# top.net
KiCad netlist of a schematic drawn in Altium Designer
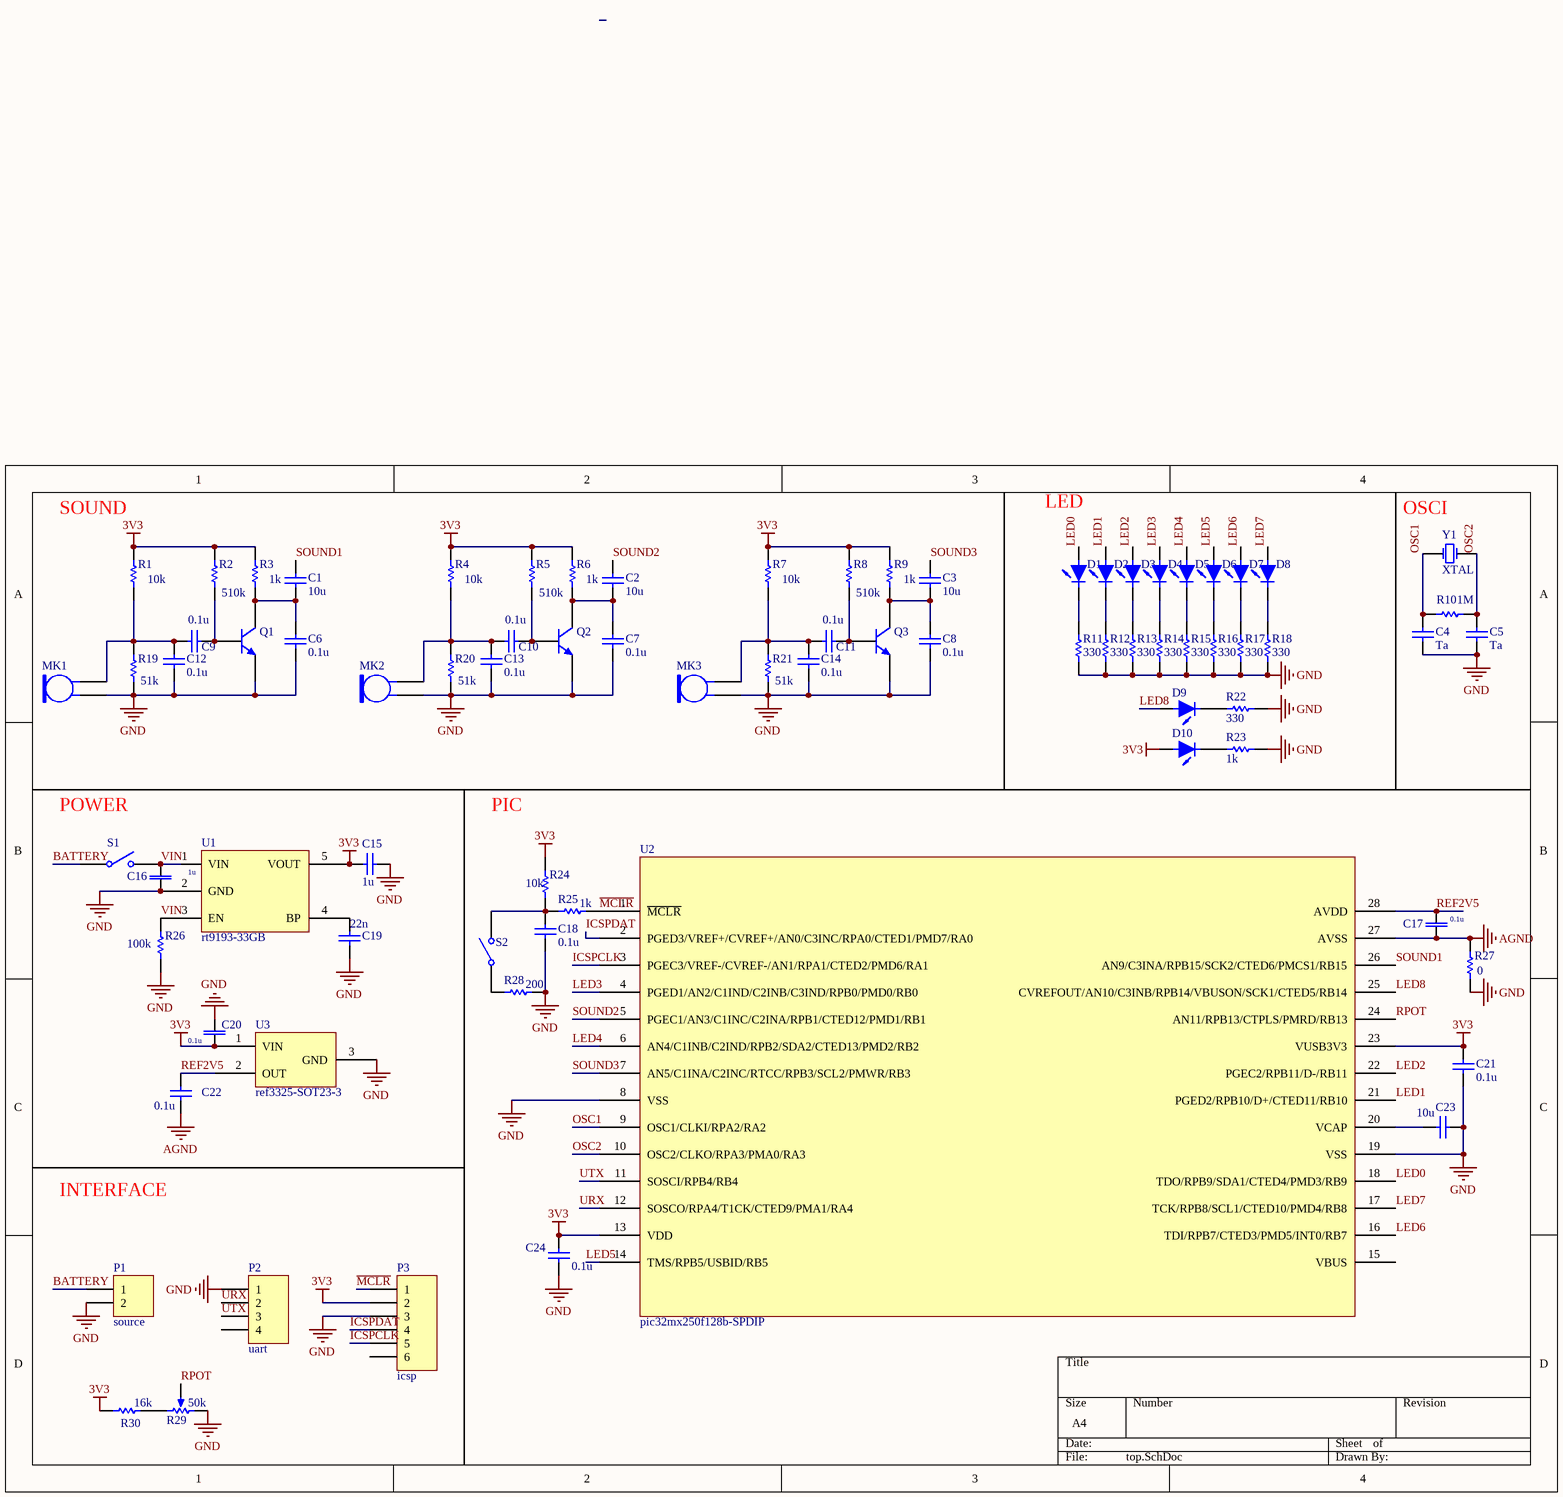
[diagram p0: top.SchDoc]

(export (version "E")
  (design (tool "Eeschema 10.0.6"))
  (components
    (comp (ref "C1")
      (value "10u")
      (footprint "CAPC1608N")
      (description "Capacitor")
      (fields (field (name "Comment") "Cap") (field (name "PUBLISHER") "Altium Limited"))
      (libsource (lib "Miscellaneous Devices") (part "Cap"))
    )
    (comp (ref "C2")
      (value "10u")
      (footprint "CAPC1608N")
      (description "Capacitor")
      (fields (field (name "Comment") "Cap") (field (name "PUBLISHER") "Altium Limited"))
      (libsource (lib "Miscellaneous Devices") (part "Cap"))
    )
    (comp (ref "C3")
      (value "10u")
      (footprint "CAPC1608N")
      (description "Capacitor")
      (fields (field (name "Comment") "Cap") (field (name "PUBLISHER") "Altium Limited"))
      (libsource (lib "Miscellaneous Devices") (part "Cap"))
    )
    (comp (ref "C4")
      (value "Ta")
      (footprint "CAPC1608N")
      (description "Capacitor")
      (fields (field (name "PUBLISHER") "Altium Limited"))
      (libsource (lib "Miscellaneous Devices") (part "Cap"))
    )
    (comp (ref "C5")
      (value "Ta")
      (footprint "CAPC1608N")
      (description "Capacitor")
      (fields (field (name "PUBLISHER") "Altium Limited"))
      (libsource (lib "Miscellaneous Devices") (part "Cap"))
    )
    (comp (ref "C6")
      (value "0.1u")
      (footprint "CAPC1608N")
      (description "Capacitor")
      (fields (field (name "Comment") "Cap") (field (name "PUBLISHER") "Altium Limited"))
      (libsource (lib "Miscellaneous Devices") (part "Cap"))
    )
    (comp (ref "C7")
      (value "0.1u")
      (footprint "CAPC1608N")
      (description "Capacitor")
      (fields (field (name "Comment") "Cap") (field (name "PUBLISHER") "Altium Limited"))
      (libsource (lib "Miscellaneous Devices") (part "Cap"))
    )
    (comp (ref "C8")
      (value "0.1u")
      (footprint "CAPC1608N")
      (description "Capacitor")
      (fields (field (name "Comment") "Cap") (field (name "PUBLISHER") "Altium Limited"))
      (libsource (lib "Miscellaneous Devices") (part "Cap"))
    )
    (comp (ref "C9")
      (value "0.1u")
      (footprint "CAPC1608N")
      (description "Capacitor")
      (fields (field (name "Comment") "Cap") (field (name "PUBLISHER") "Altium Limited"))
      (libsource (lib "Miscellaneous Devices") (part "Cap"))
    )
    (comp (ref "C10")
      (value "0.1u")
      (footprint "CAPC1608N")
      (description "Capacitor")
      (fields (field (name "Comment") "Cap") (field (name "PUBLISHER") "Altium Limited"))
      (libsource (lib "Miscellaneous Devices") (part "Cap"))
    )
    (comp (ref "C11")
      (value "0.1u")
      (footprint "CAPC1608N")
      (description "Capacitor")
      (fields (field (name "Comment") "Cap") (field (name "PUBLISHER") "Altium Limited"))
      (libsource (lib "Miscellaneous Devices") (part "Cap"))
    )
    (comp (ref "C12")
      (value "0.1u")
      (footprint "CAPC1608N")
      (description "Capacitor")
      (fields (field (name "Comment") "Cap") (field (name "PUBLISHER") "Altium Limited"))
      (libsource (lib "Miscellaneous Devices") (part "Cap"))
    )
    (comp (ref "C13")
      (value "0.1u")
      (footprint "CAPC1608N")
      (description "Capacitor")
      (fields (field (name "Comment") "Cap") (field (name "PUBLISHER") "Altium Limited"))
      (libsource (lib "Miscellaneous Devices") (part "Cap"))
    )
    (comp (ref "C14")
      (value "0.1u")
      (footprint "CAPC1608N")
      (description "Capacitor")
      (fields (field (name "Comment") "Cap") (field (name "PUBLISHER") "Altium Limited"))
      (libsource (lib "Miscellaneous Devices") (part "Cap"))
    )
    (comp (ref "C15")
      (value "1u")
      (footprint "CAPC1608N")
      (description "Capacitor")
      (fields (field (name "Comment") "Cap") (field (name "PUBLISHER") "Altium Limited"))
      (libsource (lib "Miscellaneous Devices") (part "Cap"))
    )
    (comp (ref "C16")
      (value "1u")
      (footprint "CAPC1608N")
      (description "Capacitor")
      (fields (field (name "Comment") "Cap") (field (name "PUBLISHER") "Altium Limited"))
      (libsource (lib "") (part "Cap_1"))
    )
    (comp (ref "C17")
      (value "0.1u")
      (footprint "CAPC1608N")
      (description "Capacitor")
      (fields (field (name "Comment") "Cap") (field (name "PUBLISHER") "Altium Limited"))
      (libsource (lib "") (part "Cap_1"))
    )
    (comp (ref "C18")
      (value "0.1u")
      (footprint "CAPC1608N")
      (description "Capacitor")
      (fields (field (name "Comment") "Cap") (field (name "PUBLISHER") "Altium Limited"))
      (libsource (lib "Miscellaneous Devices") (part "Cap"))
    )
    (comp (ref "C19")
      (value "22n")
      (footprint "CAPC1608N")
      (description "Capacitor")
      (fields (field (name "Comment") "Cap") (field (name "PUBLISHER") "Altium Limited"))
      (libsource (lib "Miscellaneous Devices") (part "Cap"))
    )
    (comp (ref "C20")
      (value "0.1u")
      (footprint "CAPC1608N")
      (description "Capacitor")
      (fields (field (name "Comment") "Cap") (field (name "PUBLISHER") "Altium Limited"))
      (libsource (lib "") (part "Cap_1"))
    )
    (comp (ref "C21")
      (value "0.1u")
      (footprint "CAPC1608N")
      (description "Capacitor")
      (fields (field (name "Comment") "Cap") (field (name "PUBLISHER") "Altium Limited"))
      (libsource (lib "Miscellaneous Devices") (part "Cap"))
    )
    (comp (ref "C22")
      (value "0.1u")
      (footprint "CAPC1608N")
      (description "Capacitor")
      (fields (field (name "Comment") "Cap") (field (name "PUBLISHER") "Altium Limited"))
      (libsource (lib "Miscellaneous Devices") (part "Cap"))
    )
    (comp (ref "C23")
      (value "10u")
      (footprint "CAPC1608N")
      (description "Capacitor")
      (fields (field (name "Comment") "Cap") (field (name "PUBLISHER") "Altium Limited"))
      (libsource (lib "Miscellaneous Devices") (part "Cap"))
    )
    (comp (ref "C24")
      (value "0.1u")
      (footprint "CAPC1608N")
      (description "Capacitor")
      (fields (field (name "Comment") "Cap") (field (name "PUBLISHER") "Altium Limited"))
      (libsource (lib "Miscellaneous Devices") (part "Cap"))
    )
    (comp (ref "D1")
      (value "LED2")
      (footprint "CD1608-0603")
      (description "Typical RED, GREEN, YELLOW, AMBER GaAs LED")
      (fields (field (name "PUBLISHER") "Altium Limited"))
      (libsource (lib "Miscellaneous Devices") (part "LED2"))
    )
    (comp (ref "D2")
      (value "LED2")
      (footprint "CD1608-0603")
      (description "Typical RED, GREEN, YELLOW, AMBER GaAs LED")
      (fields (field (name "PUBLISHER") "Altium Limited"))
      (libsource (lib "Miscellaneous Devices") (part "LED2"))
    )
    (comp (ref "D3")
      (value "LED2")
      (footprint "CD1608-0603")
      (description "Typical RED, GREEN, YELLOW, AMBER GaAs LED")
      (fields (field (name "PUBLISHER") "Altium Limited"))
      (libsource (lib "Miscellaneous Devices") (part "LED2"))
    )
    (comp (ref "D4")
      (value "LED2")
      (footprint "CD1608-0603")
      (description "Typical RED, GREEN, YELLOW, AMBER GaAs LED")
      (fields (field (name "PUBLISHER") "Altium Limited"))
      (libsource (lib "Miscellaneous Devices") (part "LED2"))
    )
    (comp (ref "D5")
      (value "LED2")
      (footprint "CD1608-0603")
      (description "Typical RED, GREEN, YELLOW, AMBER GaAs LED")
      (fields (field (name "PUBLISHER") "Altium Limited"))
      (libsource (lib "Miscellaneous Devices") (part "LED2"))
    )
    (comp (ref "D6")
      (value "LED2")
      (footprint "CD1608-0603")
      (description "Typical RED, GREEN, YELLOW, AMBER GaAs LED")
      (fields (field (name "PUBLISHER") "Altium Limited"))
      (libsource (lib "Miscellaneous Devices") (part "LED2"))
    )
    (comp (ref "D7")
      (value "LED2")
      (footprint "CD1608-0603")
      (description "Typical RED, GREEN, YELLOW, AMBER GaAs LED")
      (fields (field (name "PUBLISHER") "Altium Limited"))
      (libsource (lib "Miscellaneous Devices") (part "LED2"))
    )
    (comp (ref "D8")
      (value "LED2")
      (footprint "CD1608-0603")
      (description "Typical RED, GREEN, YELLOW, AMBER GaAs LED")
      (fields (field (name "PUBLISHER") "Altium Limited"))
      (libsource (lib "Miscellaneous Devices") (part "LED2"))
    )
    (comp (ref "D9")
      (value "LED2")
      (footprint "CD1608-0603")
      (description "Typical RED, GREEN, YELLOW, AMBER GaAs LED")
      (fields (field (name "PUBLISHER") "Altium Limited"))
      (libsource (lib "Miscellaneous Devices") (part "LED2"))
    )
    (comp (ref "D10")
      (value "LED2")
      (footprint "CD1608-0603")
      (description "Typical RED, GREEN, YELLOW, AMBER GaAs LED")
      (fields (field (name "PUBLISHER") "Altium Limited"))
      (libsource (lib "Miscellaneous Devices") (part "LED2"))
    )
    (comp (ref "MK1")
      (value "Mic2")
      (footprint "MK")
      (description "Microphone")
      (fields (field (name "PUBLISHER") "Altium Limited"))
      (libsource (lib "Miscellaneous Devices") (part "Mic2"))
    )
    (comp (ref "MK2")
      (value "Mic2")
      (footprint "MK")
      (description "Microphone")
      (fields (field (name "PUBLISHER") "Altium Limited"))
      (libsource (lib "Miscellaneous Devices") (part "Mic2"))
    )
    (comp (ref "MK3")
      (value "Mic2")
      (footprint "MK")
      (description "Microphone")
      (fields (field (name "PUBLISHER") "Altium Limited"))
      (libsource (lib "Miscellaneous Devices") (part "Mic2"))
    )
    (comp (ref "P1")
      (value "source")
      (footprint "HDR1X2")
      (description "Header, 2-Pin")
      (fields (field (name "PUBLISHER") "Altium Limited"))
      (libsource (lib "Miscellaneous Connectors") (part "Header 2"))
    )
    (comp (ref "P2")
      (value "uart")
      (footprint "HDR1X4")
      (description "Header, 4-Pin")
      (fields (field (name "PUBLISHER") "Altium Limited"))
      (libsource (lib "Miscellaneous Connectors") (part "Header 4"))
    )
    (comp (ref "P3")
      (value "icsp")
      (footprint "HDR1X6")
      (description "Header, 6-Pin")
      (fields (field (name "PUBLISHER") "Altium Limited"))
      (libsource (lib "Miscellaneous Connectors") (part "Header 6"))
    )
    (comp (ref "Q1")
      (value "QNPN")
      (footprint "SOT-23B_N")
      (description "NPN Bipolar Transistor")
      (fields (field (name "PUBLISHER") "Altium Limited"))
      (libsource (lib "Miscellaneous Devices") (part "QNPN"))
    )
    (comp (ref "Q2")
      (value "QNPN")
      (footprint "SOT-23B_N")
      (description "NPN Bipolar Transistor")
      (fields (field (name "PUBLISHER") "Altium Limited"))
      (libsource (lib "Miscellaneous Devices") (part "QNPN"))
    )
    (comp (ref "Q3")
      (value "QNPN")
      (footprint "SOT-23B_N")
      (description "NPN Bipolar Transistor")
      (fields (field (name "PUBLISHER") "Altium Limited"))
      (libsource (lib "Miscellaneous Devices") (part "QNPN"))
    )
    (comp (ref "R1")
      (value "10k")
      (footprint "RESC1608N")
      (description "Resistor")
      (fields (field (name "Comment") "Res1") (field (name "PUBLISHER") "Altium Limited"))
      (libsource (lib "Miscellaneous Devices") (part "Res1"))
    )
    (comp (ref "R2")
      (value "510k")
      (footprint "RESC1608N")
      (description "Resistor")
      (fields (field (name "Comment") "Res1") (field (name "PUBLISHER") "Altium Limited"))
      (libsource (lib "Miscellaneous Devices") (part "Res1"))
    )
    (comp (ref "R3")
      (value "1k")
      (footprint "RESC1608N")
      (description "Resistor")
      (fields (field (name "Comment") "Res1") (field (name "PUBLISHER") "Altium Limited"))
      (libsource (lib "Miscellaneous Devices") (part "Res1"))
    )
    (comp (ref "R4")
      (value "10k")
      (footprint "RESC1608N")
      (description "Resistor")
      (fields (field (name "Comment") "Res1") (field (name "PUBLISHER") "Altium Limited"))
      (libsource (lib "Miscellaneous Devices") (part "Res1"))
    )
    (comp (ref "R5")
      (value "510k")
      (footprint "RESC1608N")
      (description "Resistor")
      (fields (field (name "Comment") "Res1") (field (name "PUBLISHER") "Altium Limited"))
      (libsource (lib "Miscellaneous Devices") (part "Res1"))
    )
    (comp (ref "R6")
      (value "1k")
      (footprint "RESC1608N")
      (description "Resistor")
      (fields (field (name "Comment") "Res1") (field (name "PUBLISHER") "Altium Limited"))
      (libsource (lib "Miscellaneous Devices") (part "Res1"))
    )
    (comp (ref "R7")
      (value "10k")
      (footprint "RESC1608N")
      (description "Resistor")
      (fields (field (name "Comment") "Res1") (field (name "PUBLISHER") "Altium Limited"))
      (libsource (lib "Miscellaneous Devices") (part "Res1"))
    )
    (comp (ref "R8")
      (value "510k")
      (footprint "RESC1608N")
      (description "Resistor")
      (fields (field (name "Comment") "Res1") (field (name "PUBLISHER") "Altium Limited"))
      (libsource (lib "Miscellaneous Devices") (part "Res1"))
    )
    (comp (ref "R9")
      (value "1k")
      (footprint "RESC1608N")
      (description "Resistor")
      (fields (field (name "Comment") "Res1") (field (name "PUBLISHER") "Altium Limited"))
      (libsource (lib "Miscellaneous Devices") (part "Res1"))
    )
    (comp (ref "R10")
      (value "1M")
      (footprint "RESC1608N")
      (description "Resistor")
      (fields (field (name "Comment") "Res1") (field (name "PUBLISHER") "Altium Limited"))
      (libsource (lib "Miscellaneous Devices") (part "Res1"))
    )
    (comp (ref "R11")
      (value "330")
      (footprint "RESC1608N")
      (description "Resistor")
      (fields (field (name "Comment") "Res1") (field (name "PUBLISHER") "Altium Limited"))
      (libsource (lib "Miscellaneous Devices") (part "Res1"))
    )
    (comp (ref "R12")
      (value "330")
      (footprint "RESC1608N")
      (description "Resistor")
      (fields (field (name "Comment") "Res1") (field (name "PUBLISHER") "Altium Limited"))
      (libsource (lib "Miscellaneous Devices") (part "Res1"))
    )
    (comp (ref "R13")
      (value "330")
      (footprint "RESC1608N")
      (description "Resistor")
      (fields (field (name "Comment") "Res1") (field (name "PUBLISHER") "Altium Limited"))
      (libsource (lib "Miscellaneous Devices") (part "Res1"))
    )
    (comp (ref "R14")
      (value "330")
      (footprint "RESC1608N")
      (description "Resistor")
      (fields (field (name "Comment") "Res1") (field (name "PUBLISHER") "Altium Limited"))
      (libsource (lib "Miscellaneous Devices") (part "Res1"))
    )
    (comp (ref "R15")
      (value "330")
      (footprint "RESC1608N")
      (description "Resistor")
      (fields (field (name "Comment") "Res1") (field (name "PUBLISHER") "Altium Limited"))
      (libsource (lib "Miscellaneous Devices") (part "Res1"))
    )
    (comp (ref "R16")
      (value "330")
      (footprint "RESC1608N")
      (description "Resistor")
      (fields (field (name "Comment") "Res1") (field (name "PUBLISHER") "Altium Limited"))
      (libsource (lib "Miscellaneous Devices") (part "Res1"))
    )
    (comp (ref "R17")
      (value "330")
      (footprint "RESC1608N")
      (description "Resistor")
      (fields (field (name "Comment") "Res1") (field (name "PUBLISHER") "Altium Limited"))
      (libsource (lib "Miscellaneous Devices") (part "Res1"))
    )
    (comp (ref "R18")
      (value "330")
      (footprint "RESC1608N")
      (description "Resistor")
      (fields (field (name "Comment") "Res1") (field (name "PUBLISHER") "Altium Limited"))
      (libsource (lib "Miscellaneous Devices") (part "Res1"))
    )
    (comp (ref "R19")
      (value "51k")
      (footprint "RESC1608N")
      (description "Resistor")
      (fields (field (name "Comment") "Res1") (field (name "PUBLISHER") "Altium Limited"))
      (libsource (lib "Miscellaneous Devices") (part "Res1"))
    )
    (comp (ref "R20")
      (value "51k")
      (footprint "RESC1608N")
      (description "Resistor")
      (fields (field (name "Comment") "Res1") (field (name "PUBLISHER") "Altium Limited"))
      (libsource (lib "Miscellaneous Devices") (part "Res1"))
    )
    (comp (ref "R21")
      (value "51k")
      (footprint "RESC1608N")
      (description "Resistor")
      (fields (field (name "Comment") "Res1") (field (name "PUBLISHER") "Altium Limited"))
      (libsource (lib "Miscellaneous Devices") (part "Res1"))
    )
    (comp (ref "R22")
      (value "330")
      (footprint "RESC1608N")
      (description "Resistor")
      (fields (field (name "Comment") "Res1") (field (name "PUBLISHER") "Altium Limited"))
      (libsource (lib "Miscellaneous Devices") (part "Res1"))
    )
    (comp (ref "R23")
      (value "1k")
      (footprint "RESC1608N")
      (description "Resistor")
      (fields (field (name "Comment") "Res1") (field (name "PUBLISHER") "Altium Limited"))
      (libsource (lib "Miscellaneous Devices") (part "Res1"))
    )
    (comp (ref "R24")
      (value "10k")
      (footprint "RESC1608N")
      (description "Resistor")
      (fields (field (name "Comment") "Res1") (field (name "PUBLISHER") "Altium Limited"))
      (libsource (lib "Miscellaneous Devices") (part "Res1"))
    )
    (comp (ref "R25")
      (value "1k")
      (footprint "RESC1608N")
      (description "Resistor")
      (fields (field (name "Comment") "Res1") (field (name "PUBLISHER") "Altium Limited"))
      (libsource (lib "Miscellaneous Devices") (part "Res1"))
    )
    (comp (ref "R26")
      (value "100k")
      (footprint "RESC1608N")
      (description "Resistor")
      (fields (field (name "Comment") "Res1") (field (name "PUBLISHER") "Altium Limited"))
      (libsource (lib "Miscellaneous Devices") (part "Res1"))
    )
    (comp (ref "R27")
      (value "0")
      (footprint "RESC1608N")
      (description "Resistor")
      (fields (field (name "Comment") "Res1") (field (name "PUBLISHER") "Altium Limited"))
      (libsource (lib "Miscellaneous Devices") (part "Res1"))
    )
    (comp (ref "R28")
      (value "200")
      (footprint "RESC1608N")
      (description "Resistor")
      (fields (field (name "Comment") "Res1") (field (name "PUBLISHER") "Altium Limited"))
      (libsource (lib "Miscellaneous Devices") (part "Res1"))
    )
    (comp (ref "R29")
      (value "50k")
      (footprint "RPOT")
      (description "Potentiometer")
      (fields (field (name "Comment") "RPot") (field (name "PUBLISHER") "Altium Limited"))
      (libsource (lib "Miscellaneous Devices") (part "RPot"))
    )
    (comp (ref "R30")
      (value "16k")
      (footprint "RESC1608N")
      (description "Resistor")
      (fields (field (name "Comment") "Res1") (field (name "PUBLISHER") "Altium Limited"))
      (libsource (lib "Miscellaneous Devices") (part "Res1"))
    )
    (comp (ref "S1")
      (value "SW-SPST")
      (footprint "PIN3")
      (description "Single-Pole, Single-Throw Switch")
      (fields (field (name "PUBLISHER") "Altium Limited"))
      (libsource (lib "Miscellaneous Devices") (part "SW-SPST"))
    )
    (comp (ref "S2")
      (value "SW-SPST")
      (footprint "sw")
      (description "Single-Pole, Single-Throw Switch")
      (fields (field (name "PUBLISHER") "Altium Limited"))
      (libsource (lib "Miscellaneous Devices") (part "SW-SPST"))
    )
    (comp (ref "U1")
      (value "rt9193-33GB")
      (footprint "SOT23-5_N")
      (description "rt9193")
      (libsource (lib "rt9193") (part "rt9193"))
    )
    (comp (ref "U2")
      (value "pic32mx250f128b-SPDIP")
      (footprint "DIP-28")
      (libsource (lib "Schlib1") (part "pic32mx250f128b"))
    )
    (comp (ref "U3")
      (value "ref3325-SOT23-3")
      (footprint "SOT23-3")
      (description "ref33xx")
      (libsource (lib "ref33xx") (part "ref33xx"))
    )
    (comp (ref "Y1")
      (value "XTAL")
      (footprint "XTAL")
      (description "Crystal Oscillator")
      (fields (field (name "PUBLISHER") "Altium Limited"))
      (libsource (lib "Miscellaneous Devices") (part "XTAL"))
    )
  )
  (nets
    (net (code "1") (name "/BATTERY") (class "Default")
      (node (ref "P1") (pin "1") (pinfunction "1_1") (pintype "passive"))
      (node (ref "S1") (pin "1") (pinfunction "COMMON_1") (pintype "passive"))
    )
    (net (code "2") (name "/ICSPCLK") (class "Default")
      (node (ref "P3") (pin "5") (pinfunction "5_5") (pintype "passive"))
      (node (ref "U2") (pin "3") (pinfunction "PGEC3/VREF-/CVREF-/AN1/RPA1/CTED2/PMD6/RA1_3") (pintype "passive"))
    )
    (net (code "3") (name "/ICSPDAT") (class "Default")
      (node (ref "P3") (pin "4") (pinfunction "4_4") (pintype "passive"))
      (node (ref "U2") (pin "2") (pinfunction "PGED3/VREF+/CVREF+/AN0/C3INC/RPA0/CTED1/PMD7/RA0_2") (pintype "passive"))
    )
    (net (code "4") (name "/LED0") (class "Default")
      (node (ref "D1") (pin "1") (pinfunction "A_1") (pintype "passive"))
      (node (ref "U2") (pin "18") (pinfunction "TDO/RPB9/SDA1/CTED4/PMD3/RB9_18") (pintype "passive"))
    )
    (net (code "5") (name "/LED1") (class "Default")
      (node (ref "D2") (pin "1") (pinfunction "A_1") (pintype "passive"))
      (node (ref "U2") (pin "21") (pinfunction "PGED2/RPB10/D+/CTED11/RB10_21") (pintype "passive"))
    )
    (net (code "6") (name "/LED2") (class "Default")
      (node (ref "D3") (pin "1") (pinfunction "A_1") (pintype "passive"))
      (node (ref "U2") (pin "22") (pinfunction "PGEC2/RPB11/D-/RB11_22") (pintype "passive"))
    )
    (net (code "7") (name "/LED3") (class "Default")
      (node (ref "D4") (pin "1") (pinfunction "A_1") (pintype "passive"))
      (node (ref "U2") (pin "4") (pinfunction "PGED1/AN2/C1IND/C2INB/C3IND/RPB0/PMD0/RB0_4") (pintype "passive"))
    )
    (net (code "8") (name "/LED4") (class "Default")
      (node (ref "D5") (pin "1") (pinfunction "A_1") (pintype "passive"))
      (node (ref "U2") (pin "6") (pinfunction "AN4/C1INB/C2IND/RPB2/SDA2/CTED13/PMD2/RB2_6") (pintype "passive"))
    )
    (net (code "9") (name "/LED5") (class "Default")
      (node (ref "D6") (pin "1") (pinfunction "A_1") (pintype "passive"))
      (node (ref "U2") (pin "14") (pinfunction "TMS/RPB5/USBID/RB5_14") (pintype "passive"))
    )
    (net (code "10") (name "/LED6") (class "Default")
      (node (ref "D7") (pin "1") (pinfunction "A_1") (pintype "passive"))
      (node (ref "U2") (pin "16") (pinfunction "TDI/RPB7/CTED3/PMD5/INT0/RB7_16") (pintype "passive"))
    )
    (net (code "11") (name "/LED7") (class "Default")
      (node (ref "D8") (pin "1") (pinfunction "A_1") (pintype "passive"))
      (node (ref "U2") (pin "17") (pinfunction "TCK/RPB8/SCL1/CTED10/PMD4/RB8_17") (pintype "passive"))
    )
    (net (code "12") (name "/LED8") (class "Default")
      (node (ref "D9") (pin "1") (pinfunction "A_1") (pintype "passive"))
      (node (ref "U2") (pin "25") (pinfunction "CVREFOUT/AN10/C3INB/RPB14/VBUSON/SCK1/CTED5/RB14_25") (pintype "passive"))
    )
    (net (code "13") (name "/OSC1") (class "Default")
      (node (ref "C4") (pin "1") (pinfunction "1_1") (pintype "passive"))
      (node (ref "R10") (pin "1") (pinfunction "1_1") (pintype "passive"))
      (node (ref "U2") (pin "9") (pinfunction "OSC1/CLKI/RPA2/RA2_9") (pintype "passive"))
      (node (ref "Y1") (pin "2") (pinfunction "OSC2_2") (pintype "passive"))
    )
    (net (code "14") (name "/OSC2") (class "Default")
      (node (ref "C5") (pin "1") (pinfunction "1_1") (pintype "passive"))
      (node (ref "R10") (pin "2") (pinfunction "2_2") (pintype "passive"))
      (node (ref "U2") (pin "10") (pinfunction "OSC2/CLKO/RPA3/PMA0/RA3_10") (pintype "passive"))
      (node (ref "Y1") (pin "1") (pinfunction "OSC1_1") (pintype "passive"))
    )
    (net (code "15") (name "/REF2V5") (class "Default")
      (node (ref "C17") (pin "1") (pinfunction "1_1") (pintype "passive"))
      (node (ref "C22") (pin "2") (pinfunction "2_2") (pintype "passive"))
      (node (ref "U2") (pin "28") (pinfunction "AVDD_28") (pintype "passive"))
      (node (ref "U3") (pin "2") (pinfunction "OUT_2") (pintype "passive"))
    )
    (net (code "16") (name "/RPOT") (class "Default")
      (node (ref "R29") (pin "3") (pinfunction "TAP_3") (pintype "passive"))
      (node (ref "U2") (pin "24") (pinfunction "AN11/RPB13/CTPLS/PMRD/RB13_24") (pintype "passive"))
    )
    (net (code "17") (name "/SOUND1") (class "Default")
      (node (ref "C1") (pin "2") (pinfunction "2_2") (pintype "passive"))
      (node (ref "U2") (pin "26") (pinfunction "AN9/C3INA/RPB15/SCK2/CTED6/PMCS1/RB15_26") (pintype "passive"))
    )
    (net (code "18") (name "/SOUND2") (class "Default")
      (node (ref "C2") (pin "2") (pinfunction "2_2") (pintype "passive"))
      (node (ref "U2") (pin "5") (pinfunction "PGEC1/AN3/C1INC/C2INA/RPB1/CTED12/PMD1/RB1_5") (pintype "passive"))
    )
    (net (code "19") (name "/SOUND3") (class "Default")
      (node (ref "C3") (pin "2") (pinfunction "2_2") (pintype "passive"))
      (node (ref "U2") (pin "7") (pinfunction "AN5/C1INA/C2INC/RTCC/RPB3/SCL2/PMWR/RB3_7") (pintype "passive"))
    )
    (net (code "20") (name "/URX") (class "Default")
      (node (ref "P2") (pin "2") (pinfunction "2_2") (pintype "passive"))
      (node (ref "U2") (pin "12") (pinfunction "SOSCO/RPA4/T1CK/CTED9/PMA1/RA4_12") (pintype "passive"))
    )
    (net (code "21") (name "/UTX") (class "Default")
      (node (ref "P2") (pin "3") (pinfunction "3_3") (pintype "passive"))
      (node (ref "U2") (pin "11") (pinfunction "SOSCI/RPB4/RB4_11") (pintype "passive"))
    )
    (net (code "22") (name "/VIN") (class "Default")
      (node (ref "C16") (pin "1") (pinfunction "1_1") (pintype "passive"))
      (node (ref "R26") (pin "2") (pinfunction "2_2") (pintype "passive"))
      (node (ref "S1") (pin "2") (pinfunction "NO_2") (pintype "passive"))
      (node (ref "U1") (pin "1") (pinfunction "VIN_1") (pintype "passive"))
      (node (ref "U1") (pin "3") (pinfunction "EN_3") (pintype "passive"))
    )
    (net (code "23") (name "/~{MCLR}") (class "Default")
      (node (ref "P3") (pin "1") (pinfunction "1_1") (pintype "passive"))
      (node (ref "R25") (pin "1") (pinfunction "1_1") (pintype "passive"))
      (node (ref "U2") (pin "1") (pinfunction "~{MCLR}_1") (pintype "passive"))
    )
    (net (code "24") (name "3V3") (class "Default")
      (node (ref "C15") (pin "2") (pinfunction "2_2") (pintype "passive"))
      (node (ref "C20") (pin "2") (pinfunction "2_2") (pintype "passive"))
      (node (ref "C21") (pin "1") (pinfunction "1_1") (pintype "passive"))
      (node (ref "C24") (pin "1") (pinfunction "1_1") (pintype "passive"))
      (node (ref "D10") (pin "1") (pinfunction "A_1") (pintype "passive"))
      (node (ref "P3") (pin "2") (pinfunction "2_2") (pintype "passive"))
      (node (ref "R1") (pin "2") (pinfunction "2_2") (pintype "passive"))
      (node (ref "R2") (pin "1") (pinfunction "1_1") (pintype "passive"))
      (node (ref "R24") (pin "2") (pinfunction "2_2") (pintype "passive"))
      (node (ref "R3") (pin "1") (pinfunction "1_1") (pintype "passive"))
      (node (ref "R30") (pin "2") (pinfunction "2_2") (pintype "passive"))
      (node (ref "R4") (pin "2") (pinfunction "2_2") (pintype "passive"))
      (node (ref "R5") (pin "1") (pinfunction "1_1") (pintype "passive"))
      (node (ref "R6") (pin "1") (pinfunction "1_1") (pintype "passive"))
      (node (ref "R7") (pin "2") (pinfunction "2_2") (pintype "passive"))
      (node (ref "R8") (pin "1") (pinfunction "1_1") (pintype "passive"))
      (node (ref "R9") (pin "1") (pinfunction "1_1") (pintype "passive"))
      (node (ref "U1") (pin "5") (pinfunction "VOUT_5") (pintype "passive"))
      (node (ref "U2") (pin "13") (pinfunction "VDD_13") (pintype "passive"))
      (node (ref "U2") (pin "23") (pinfunction "VUSB3V3_23") (pintype "passive"))
      (node (ref "U3") (pin "1") (pinfunction "VIN_1") (pintype "passive"))
    )
    (net (code "25") (name "AGND") (class "Default")
      (node (ref "C17") (pin "2") (pinfunction "2_2") (pintype "passive"))
      (node (ref "C22") (pin "1") (pinfunction "1_1") (pintype "passive"))
      (node (ref "R27") (pin "1") (pinfunction "1_1") (pintype "passive"))
      (node (ref "U2") (pin "27") (pinfunction "AVSS_27") (pintype "passive"))
    )
    (net (code "26") (name "GND") (class "Default")
      (node (ref "C12") (pin "2") (pinfunction "2_2") (pintype "passive"))
      (node (ref "C13") (pin "2") (pinfunction "2_2") (pintype "passive"))
      (node (ref "C14") (pin "2") (pinfunction "2_2") (pintype "passive"))
      (node (ref "C15") (pin "1") (pinfunction "1_1") (pintype "passive"))
      (node (ref "C16") (pin "2") (pinfunction "2_2") (pintype "passive"))
      (node (ref "C18") (pin "2") (pinfunction "2_2") (pintype "passive"))
      (node (ref "C19") (pin "1") (pinfunction "1_1") (pintype "passive"))
      (node (ref "C20") (pin "1") (pinfunction "1_1") (pintype "passive"))
      (node (ref "C21") (pin "2") (pinfunction "2_2") (pintype "passive"))
      (node (ref "C23") (pin "1") (pinfunction "1_1") (pintype "passive"))
      (node (ref "C24") (pin "2") (pinfunction "2_2") (pintype "passive"))
      (node (ref "C4") (pin "2") (pinfunction "2_2") (pintype "passive"))
      (node (ref "C5") (pin "2") (pinfunction "2_2") (pintype "passive"))
      (node (ref "C6") (pin "2") (pinfunction "2_2") (pintype "passive"))
      (node (ref "C7") (pin "2") (pinfunction "2_2") (pintype "passive"))
      (node (ref "C8") (pin "2") (pinfunction "2_2") (pintype "passive"))
      (node (ref "MK1") (pin "1") (pinfunction "1_1") (pintype "passive"))
      (node (ref "MK2") (pin "1") (pinfunction "1_1") (pintype "passive"))
      (node (ref "MK3") (pin "1") (pinfunction "1_1") (pintype "passive"))
      (node (ref "P1") (pin "2") (pinfunction "2_2") (pintype "passive"))
      (node (ref "P2") (pin "1") (pinfunction "1_1") (pintype "passive"))
      (node (ref "P3") (pin "3") (pinfunction "3_3") (pintype "passive"))
      (node (ref "Q1") (pin "3") (pinfunction "E_3") (pintype "passive"))
      (node (ref "Q2") (pin "3") (pinfunction "E_3") (pintype "passive"))
      (node (ref "Q3") (pin "3") (pinfunction "E_3") (pintype "passive"))
      (node (ref "R11") (pin "1") (pinfunction "1_1") (pintype "passive"))
      (node (ref "R12") (pin "1") (pinfunction "1_1") (pintype "passive"))
      (node (ref "R13") (pin "1") (pinfunction "1_1") (pintype "passive"))
      (node (ref "R14") (pin "1") (pinfunction "1_1") (pintype "passive"))
      (node (ref "R15") (pin "1") (pinfunction "1_1") (pintype "passive"))
      (node (ref "R16") (pin "1") (pinfunction "1_1") (pintype "passive"))
      (node (ref "R17") (pin "1") (pinfunction "1_1") (pintype "passive"))
      (node (ref "R18") (pin "1") (pinfunction "1_1") (pintype "passive"))
      (node (ref "R19") (pin "2") (pinfunction "2_2") (pintype "passive"))
      (node (ref "R20") (pin "2") (pinfunction "2_2") (pintype "passive"))
      (node (ref "R21") (pin "2") (pinfunction "2_2") (pintype "passive"))
      (node (ref "R22") (pin "1") (pinfunction "1_1") (pintype "passive"))
      (node (ref "R23") (pin "1") (pinfunction "1_1") (pintype "passive"))
      (node (ref "R26") (pin "1") (pinfunction "1_1") (pintype "passive"))
      (node (ref "R27") (pin "2") (pinfunction "2_2") (pintype "passive"))
      (node (ref "R28") (pin "1") (pinfunction "1_1") (pintype "passive"))
      (node (ref "R29") (pin "1") (pinfunction "TOP_1") (pintype "passive"))
      (node (ref "U1") (pin "2") (pinfunction "GND_2") (pintype "passive"))
      (node (ref "U2") (pin "19") (pinfunction "VSS_19") (pintype "passive"))
      (node (ref "U2") (pin "8") (pinfunction "VSS_8") (pintype "passive"))
      (node (ref "U3") (pin "3") (pinfunction "GND_3") (pintype "passive"))
    )
    (net (code "27") (name "Net-(C10-Pad1)") (class "Default")
      (node (ref "C10") (pin "1") (pinfunction "1_1") (pintype "passive"))
      (node (ref "C13") (pin "1") (pinfunction "1_1") (pintype "passive"))
      (node (ref "MK2") (pin "2") (pinfunction "2_2") (pintype "passive"))
      (node (ref "R20") (pin "1") (pinfunction "1_1") (pintype "passive"))
      (node (ref "R4") (pin "1") (pinfunction "1_1") (pintype "passive"))
    )
    (net (code "28") (name "Net-(C11-Pad1)") (class "Default")
      (node (ref "C11") (pin "1") (pinfunction "1_1") (pintype "passive"))
      (node (ref "C14") (pin "1") (pinfunction "1_1") (pintype "passive"))
      (node (ref "MK3") (pin "2") (pinfunction "2_2") (pintype "passive"))
      (node (ref "R21") (pin "1") (pinfunction "1_1") (pintype "passive"))
      (node (ref "R7") (pin "1") (pinfunction "1_1") (pintype "passive"))
    )
    (net (code "29") (name "Net-(C12-Pad1)") (class "Default")
      (node (ref "C12") (pin "1") (pinfunction "1_1") (pintype "passive"))
      (node (ref "C9") (pin "1") (pinfunction "1_1") (pintype "passive"))
      (node (ref "MK1") (pin "2") (pinfunction "2_2") (pintype "passive"))
      (node (ref "R1") (pin "1") (pinfunction "1_1") (pintype "passive"))
      (node (ref "R19") (pin "1") (pinfunction "1_1") (pintype "passive"))
    )
    (net (code "30") (name "Net-(D1-K)") (class "Default")
      (node (ref "D1") (pin "2") (pinfunction "K_2") (pintype "passive"))
      (node (ref "R11") (pin "2") (pinfunction "2_2") (pintype "passive"))
    )
    (net (code "31") (name "Net-(D2-K)") (class "Default")
      (node (ref "D2") (pin "2") (pinfunction "K_2") (pintype "passive"))
      (node (ref "R12") (pin "2") (pinfunction "2_2") (pintype "passive"))
    )
    (net (code "32") (name "Net-(D3-K)") (class "Default")
      (node (ref "D3") (pin "2") (pinfunction "K_2") (pintype "passive"))
      (node (ref "R13") (pin "2") (pinfunction "2_2") (pintype "passive"))
    )
    (net (code "33") (name "Net-(D4-K)") (class "Default")
      (node (ref "D4") (pin "2") (pinfunction "K_2") (pintype "passive"))
      (node (ref "R14") (pin "2") (pinfunction "2_2") (pintype "passive"))
    )
    (net (code "34") (name "Net-(D5-K)") (class "Default")
      (node (ref "D5") (pin "2") (pinfunction "K_2") (pintype "passive"))
      (node (ref "R15") (pin "2") (pinfunction "2_2") (pintype "passive"))
    )
    (net (code "35") (name "Net-(D6-K)") (class "Default")
      (node (ref "D6") (pin "2") (pinfunction "K_2") (pintype "passive"))
      (node (ref "R16") (pin "2") (pinfunction "2_2") (pintype "passive"))
    )
    (net (code "36") (name "Net-(D7-K)") (class "Default")
      (node (ref "D7") (pin "2") (pinfunction "K_2") (pintype "passive"))
      (node (ref "R17") (pin "2") (pinfunction "2_2") (pintype "passive"))
    )
    (net (code "37") (name "Net-(D8-K)") (class "Default")
      (node (ref "D8") (pin "2") (pinfunction "K_2") (pintype "passive"))
      (node (ref "R18") (pin "2") (pinfunction "2_2") (pintype "passive"))
    )
    (net (code "38") (name "Net-(D9-K)") (class "Default")
      (node (ref "D9") (pin "2") (pinfunction "K_2") (pintype "passive"))
      (node (ref "R22") (pin "2") (pinfunction "2_2") (pintype "passive"))
    )
    (net (code "39") (name "Net-(D10-K)") (class "Default")
      (node (ref "D10") (pin "2") (pinfunction "K_2") (pintype "passive"))
      (node (ref "R23") (pin "2") (pinfunction "2_2") (pintype "passive"))
    )
    (net (code "40") (name "Net-(Q1-B)") (class "Default")
      (node (ref "C9") (pin "2") (pinfunction "2_2") (pintype "passive"))
      (node (ref "Q1") (pin "2") (pinfunction "B_2") (pintype "passive"))
      (node (ref "R2") (pin "2") (pinfunction "2_2") (pintype "passive"))
    )
    (net (code "41") (name "Net-(Q1-C)") (class "Default")
      (node (ref "C1") (pin "1") (pinfunction "1_1") (pintype "passive"))
      (node (ref "C6") (pin "1") (pinfunction "1_1") (pintype "passive"))
      (node (ref "Q1") (pin "1") (pinfunction "C_1") (pintype "passive"))
      (node (ref "R3") (pin "2") (pinfunction "2_2") (pintype "passive"))
    )
    (net (code "42") (name "Net-(Q2-B)") (class "Default")
      (node (ref "C10") (pin "2") (pinfunction "2_2") (pintype "passive"))
      (node (ref "Q2") (pin "2") (pinfunction "B_2") (pintype "passive"))
      (node (ref "R5") (pin "2") (pinfunction "2_2") (pintype "passive"))
    )
    (net (code "43") (name "Net-(Q2-C)") (class "Default")
      (node (ref "C2") (pin "1") (pinfunction "1_1") (pintype "passive"))
      (node (ref "C7") (pin "1") (pinfunction "1_1") (pintype "passive"))
      (node (ref "Q2") (pin "1") (pinfunction "C_1") (pintype "passive"))
      (node (ref "R6") (pin "2") (pinfunction "2_2") (pintype "passive"))
    )
    (net (code "44") (name "Net-(Q3-B)") (class "Default")
      (node (ref "C11") (pin "2") (pinfunction "2_2") (pintype "passive"))
      (node (ref "Q3") (pin "2") (pinfunction "B_2") (pintype "passive"))
      (node (ref "R8") (pin "2") (pinfunction "2_2") (pintype "passive"))
    )
    (net (code "45") (name "Net-(Q3-C)") (class "Default")
      (node (ref "C3") (pin "1") (pinfunction "1_1") (pintype "passive"))
      (node (ref "C8") (pin "1") (pinfunction "1_1") (pintype "passive"))
      (node (ref "Q3") (pin "1") (pinfunction "C_1") (pintype "passive"))
      (node (ref "R9") (pin "2") (pinfunction "2_2") (pintype "passive"))
    )
    (net (code "46") (name "Net-(R29-BOT)") (class "Default")
      (node (ref "R29") (pin "2") (pinfunction "BOT_2") (pintype "passive"))
      (node (ref "R30") (pin "1") (pinfunction "1_1") (pintype "passive"))
    )
    (net (code "47") (name "Net-(S2-COMMON)") (class "Default")
      (node (ref "R28") (pin "2") (pinfunction "2_2") (pintype "passive"))
      (node (ref "S2") (pin "1") (pinfunction "COMMON_1") (pintype "passive"))
    )
    (net (code "48") (name "Net-(S2-NO)") (class "Default")
      (node (ref "C18") (pin "1") (pinfunction "1_1") (pintype "passive"))
      (node (ref "R24") (pin "1") (pinfunction "1_1") (pintype "passive"))
      (node (ref "R25") (pin "2") (pinfunction "2_2") (pintype "passive"))
      (node (ref "S2") (pin "2") (pinfunction "NO_2") (pintype "passive"))
    )
    (net (code "49") (name "Net-(U1-BP)") (class "Default")
      (node (ref "C19") (pin "2") (pinfunction "2_2") (pintype "passive"))
      (node (ref "U1") (pin "4") (pinfunction "BP_4") (pintype "passive"))
    )
    (net (code "50") (name "Net-(U2-VCAP)") (class "Default")
      (node (ref "C23") (pin "2") (pinfunction "2_2") (pintype "passive"))
      (node (ref "U2") (pin "20") (pinfunction "VCAP_20") (pintype "passive"))
    )
    (net (code "51") (name "unconnected-(P2-Pad4)") (class "Default")
      (node (ref "P2") (pin "4") (pinfunction "4_4") (pintype "passive"))
    )
    (net (code "52") (name "unconnected-(P3-Pad6)") (class "Default")
      (node (ref "P3") (pin "6") (pinfunction "6_6") (pintype "passive"))
    )
    (net (code "53") (name "unconnected-(U2-VBUS-Pad15)") (class "Default")
      (node (ref "U2") (pin "15") (pinfunction "VBUS_15") (pintype "passive"))
    )
  )
)
